# topboardcombined.net
KiCad netlist of a schematic drawn in EAGLE
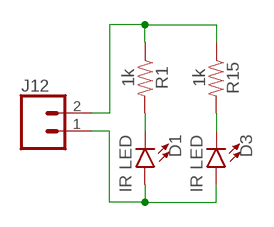
[diagram p0: schematic, sheet 1]

(export (version "E")
  (design (tool "Eeschema 10.0.6"))
  (components
    (comp (ref "D1")
      (value "IR LED")
      (footprint "eagle-import:LED-0603")
      (libsource (lib "eagle-import") (part "LED-IR0603"))
    )
    (comp (ref "D3")
      (value "IR LED")
      (footprint "eagle-import:LED-0603")
      (libsource (lib "eagle-import") (part "LED-IR0603"))
    )
    (comp (ref "J12")
      (value "CONN_02")
      (footprint "eagle-import:1X02")
      (libsource (lib "eagle-import") (part "CONN_02"))
    )
    (comp (ref "R1")
      (value "1k")
      (footprint "eagle-import:0603")
      (libsource (lib "eagle-import") (part "1KOHM-0603-1/10W-1%"))
    )
    (comp (ref "R15")
      (value "1k")
      (footprint "eagle-import:0603")
      (libsource (lib "eagle-import") (part "1KOHM-0603-1/10W-1%"))
    )
  )
  (nets
    (net (code "1") (name "Net-(D1-PadA)") (class "Default")
      (node (ref "D1") (pin "A") (pinfunction "A_A") (pintype "passive"))
      (node (ref "D3") (pin "A") (pinfunction "A_A") (pintype "passive"))
      (node (ref "J12") (pin "1") (pinfunction "1_1") (pintype "passive"))
    )
    (net (code "2") (name "Net-(D1-PadC)") (class "Default")
      (node (ref "D1") (pin "C") (pinfunction "C_C") (pintype "passive"))
      (node (ref "R1") (pin "2") (pinfunction "2_2") (pintype "passive"))
    )
    (net (code "3") (name "Net-(D3-PadC)") (class "Default")
      (node (ref "D3") (pin "C") (pinfunction "C_C") (pintype "passive"))
      (node (ref "R15") (pin "2") (pinfunction "2_2") (pintype "passive"))
    )
    (net (code "4") (name "Net-(J12-Pad2)") (class "Default")
      (node (ref "J12") (pin "2") (pinfunction "2_2") (pintype "passive"))
      (node (ref "R1") (pin "1") (pinfunction "1_1") (pintype "passive"))
      (node (ref "R15") (pin "1") (pinfunction "1_1") (pintype "passive"))
    )
  )
)
